# tr_1.net
KiCad netlist of a schematic drawn in EAGLE
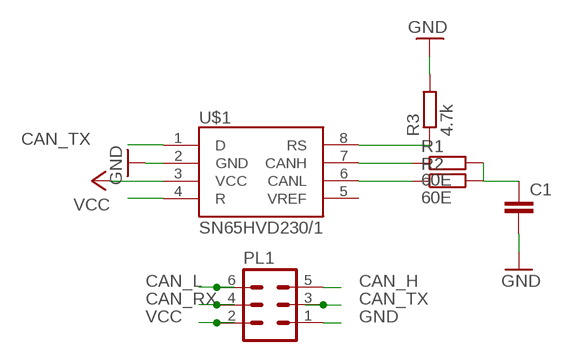
[diagram p0: schematic, sheet 1]

(export (version "E")
  (design (tool "Eeschema 10.0.6"))
  (components
    (comp (ref "C1")
      (value "C-EUC0805K")
      (footprint "eagle-import:C0805K")
      (libsource (lib "eagle-import") (part "C-EUC0805K"))
    )
    (comp (ref "PL1")
      (value "06V")
      (footprint "eagle-import:06V")
      (libsource (lib "eagle-import") (part "06V"))
    )
    (comp (ref "R1")
      (value "60E")
      (footprint "eagle-import:R0805W")
      (libsource (lib "eagle-import") (part "R-EU_R0805W"))
    )
    (comp (ref "R2")
      (value "60E")
      (footprint "eagle-import:R0805W")
      (libsource (lib "eagle-import") (part "R-EU_R0805W"))
    )
    (comp (ref "R3")
      (value "4.7k")
      (footprint "eagle-import:R0805W")
      (libsource (lib "eagle-import") (part "R-EU_R0805W"))
    )
    (comp (ref "U$1")
      (value "SN65HVD230/1")
      (footprint "eagle-import:SO8")
      (libsource (lib "eagle-import") (part "SN65HVD230/1"))
    )
  )
  (nets
    (net (code "1") (name "/CAN_H") (class "Default")
      (node (ref "PL1") (pin "5") (pinfunction "5_5") (pintype "passive"))
      (node (ref "R1") (pin "1") (pinfunction "1_1") (pintype "passive"))
      (node (ref "U$1") (pin "7") (pinfunction "CANH_7") (pintype "bidirectional"))
    )
    (net (code "2") (name "/CAN_L") (class "Default")
      (node (ref "PL1") (pin "6") (pinfunction "6_6") (pintype "passive"))
      (node (ref "R2") (pin "1") (pinfunction "1_1") (pintype "passive"))
      (node (ref "U$1") (pin "6") (pinfunction "CANL_6") (pintype "bidirectional"))
    )
    (net (code "3") (name "/CAN_RX") (class "Default")
      (node (ref "PL1") (pin "4") (pinfunction "4_4") (pintype "passive"))
      (node (ref "U$1") (pin "4") (pinfunction "R_4") (pintype "bidirectional"))
    )
    (net (code "4") (name "/CAN_TX") (class "Default")
      (node (ref "PL1") (pin "3") (pinfunction "3_3") (pintype "passive"))
      (node (ref "U$1") (pin "1") (pinfunction "D_1") (pintype "bidirectional"))
    )
    (net (code "5") (name "GND") (class "Default")
      (node (ref "C1") (pin "2") (pinfunction "2_2") (pintype "passive"))
      (node (ref "PL1") (pin "1") (pinfunction "1_1") (pintype "passive"))
      (node (ref "R3") (pin "2") (pinfunction "2_2") (pintype "passive"))
      (node (ref "U$1") (pin "2") (pinfunction "GND_2") (pintype "power_in"))
    )
    (net (code "6") (name "Net-(C1-Pad1)") (class "Default")
      (node (ref "C1") (pin "1") (pinfunction "1_1") (pintype "passive"))
      (node (ref "R1") (pin "2") (pinfunction "2_2") (pintype "passive"))
      (node (ref "R2") (pin "2") (pinfunction "2_2") (pintype "passive"))
    )
    (net (code "7") (name "Net-(U$1-RS)") (class "Default")
      (node (ref "R3") (pin "1") (pinfunction "1_1") (pintype "passive"))
      (node (ref "U$1") (pin "8") (pinfunction "RS_8") (pintype "bidirectional"))
    )
    (net (code "8") (name "VCC") (class "Default")
      (node (ref "PL1") (pin "2") (pinfunction "2_2") (pintype "passive"))
      (node (ref "U$1") (pin "3") (pinfunction "VCC_3") (pintype "power_in"))
    )
    (net (code "9") (name "unconnected-(U$1-VREF-Pad5)") (class "Default")
      (node (ref "U$1") (pin "5") (pinfunction "VREF_5") (pintype "bidirectional"))
    )
  )
)
